# pcb-meter.net
KiCad netlist of a schematic drawn in EAGLE
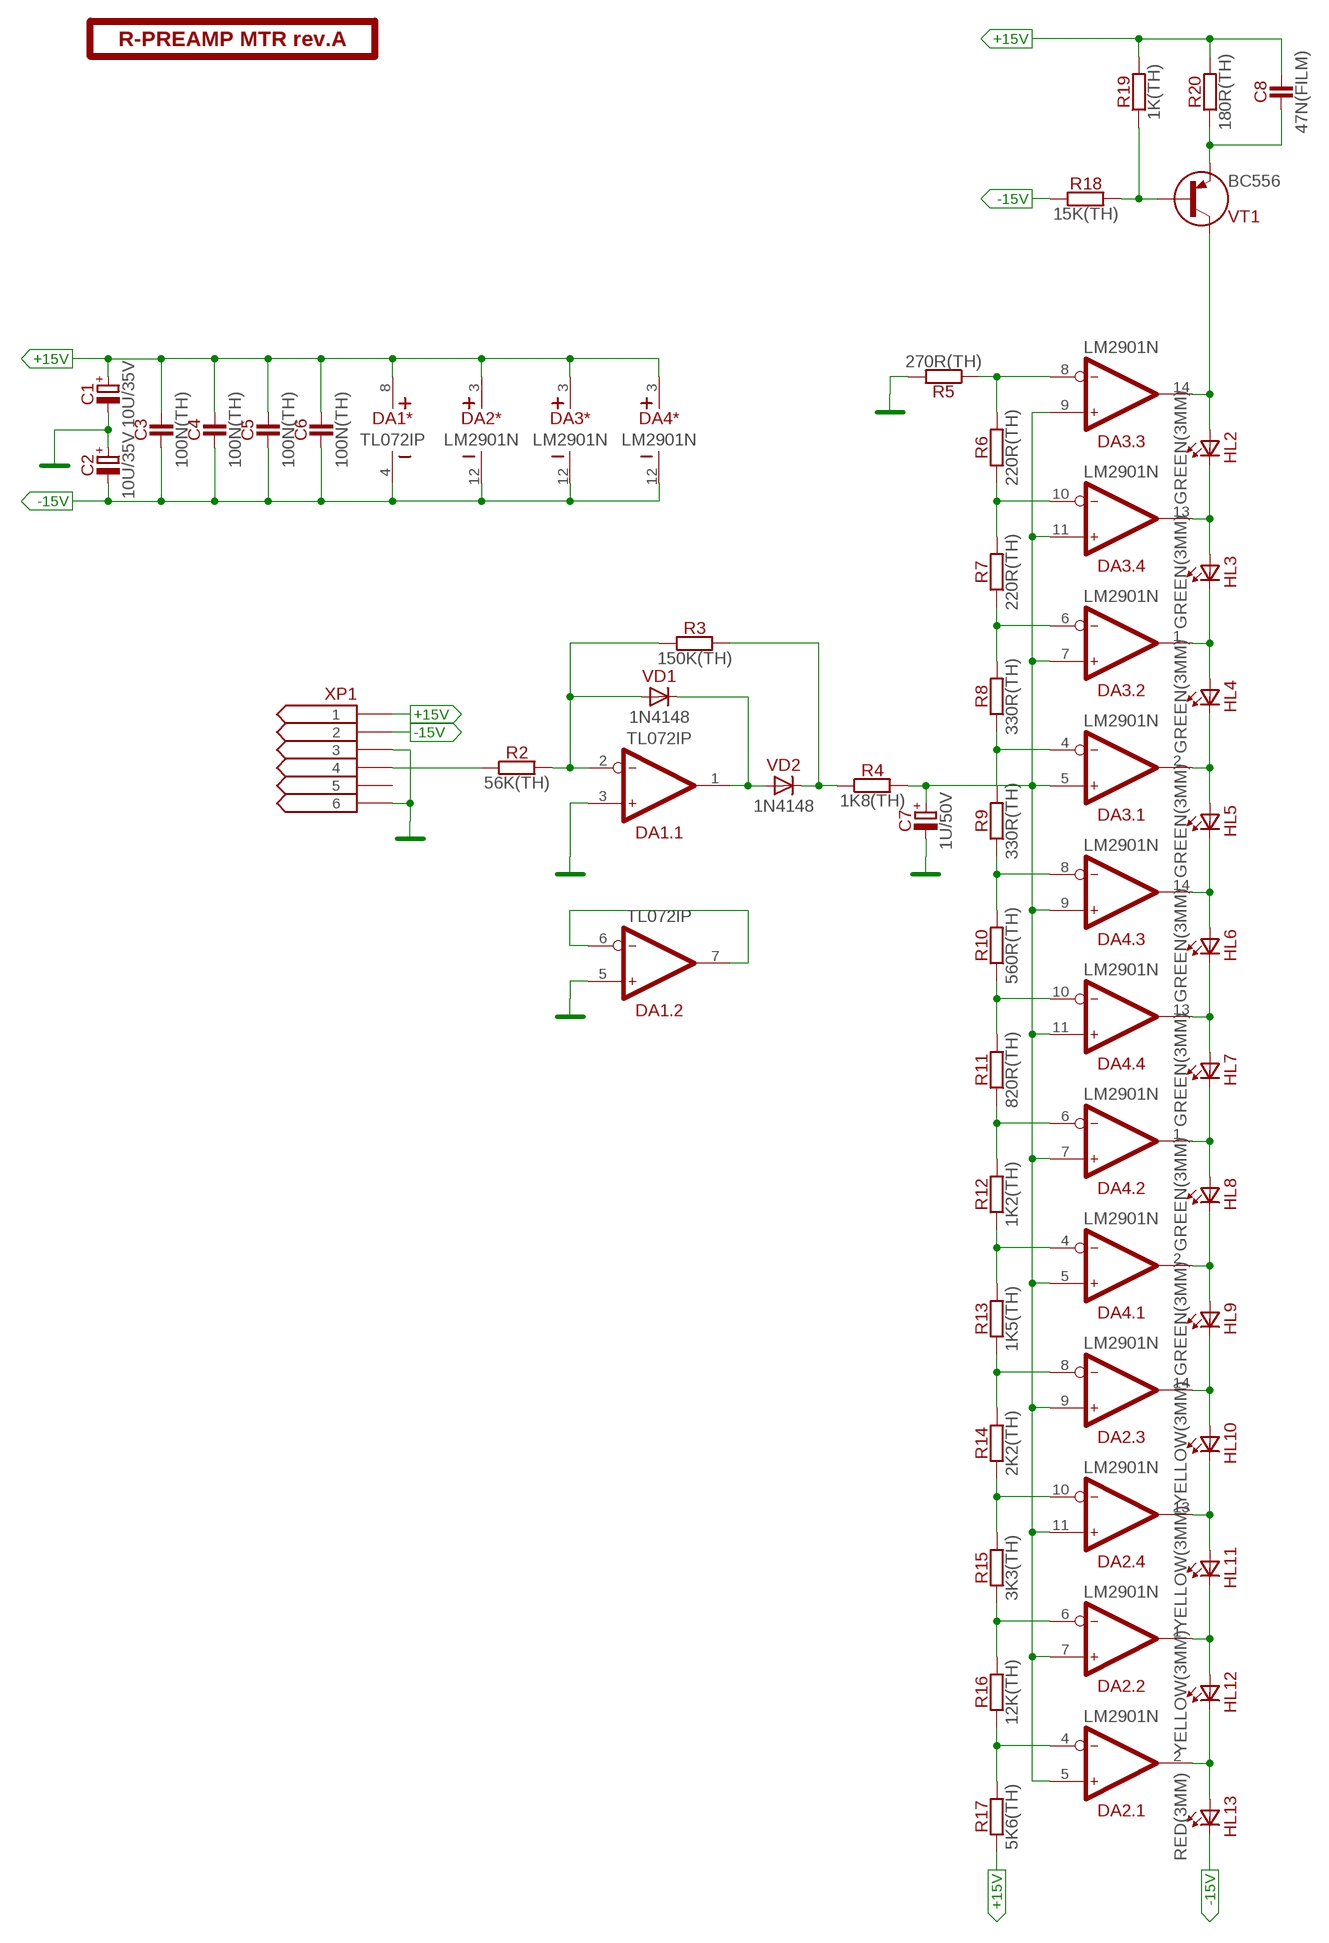
[diagram p0: schematic, sheet 1]

(export (version "E")
  (design (tool "Eeschema 10.0.6"))
  (components
    (comp (ref "C1")
      (value "10U/35V")
      (footprint "eagle-import:E2-5")
      (libsource (lib "eagle-import") (part "?10U/35V"))
    )
    (comp (ref "C2")
      (value "10U/35V")
      (footprint "eagle-import:E2-5")
      (libsource (lib "eagle-import") (part "?10U/35V"))
    )
    (comp (ref "C3")
      (value "100N(TH)")
      (footprint "eagle-import:C050-024X044")
      (libsource (lib "eagle-import") (part "?100N(TH)"))
    )
    (comp (ref "C4")
      (value "100N(TH)")
      (footprint "eagle-import:C050-024X044")
      (libsource (lib "eagle-import") (part "?100N(TH)"))
    )
    (comp (ref "C5")
      (value "100N(TH)")
      (footprint "eagle-import:C050-024X044")
      (libsource (lib "eagle-import") (part "?100N(TH)"))
    )
    (comp (ref "C6")
      (value "100N(TH)")
      (footprint "eagle-import:C050-024X044")
      (libsource (lib "eagle-import") (part "?100N(TH)"))
    )
    (comp (ref "C7")
      (value "1U/50V")
      (footprint "eagle-import:E1,5-4")
      (libsource (lib "eagle-import") (part "?1U/50V"))
    )
    (comp (ref "C8")
      (value "47N(FILM)")
      (footprint "eagle-import:C050-025X075")
      (libsource (lib "eagle-import") (part "?47N(FILM)"))
    )
    (comp (ref "DA1")
      (value "TL072IP")
      (footprint "eagle-import:DIP-8")
      (libsource (lib "eagle-import") (part "TL072IP"))
    )
    (comp (ref "DA2")
      (value "LM2901N")
      (footprint "eagle-import:DIP-14")
      (libsource (lib "eagle-import") (part "LM2901N"))
    )
    (comp (ref "DA3")
      (value "LM2901N")
      (footprint "eagle-import:DIP-14")
      (libsource (lib "eagle-import") (part "LM2901N"))
    )
    (comp (ref "DA4")
      (value "LM2901N")
      (footprint "eagle-import:DIP-14")
      (libsource (lib "eagle-import") (part "LM2901N"))
    )
    (comp (ref "HL2")
      (value "GREEN(3MM)")
      (footprint "eagle-import:LED3MM-H")
      (libsource (lib "eagle-import") (part "?(3MM)GREEN"))
    )
    (comp (ref "HL3")
      (value "GREEN(3MM)")
      (footprint "eagle-import:LED3MM-H")
      (libsource (lib "eagle-import") (part "?(3MM)GREEN"))
    )
    (comp (ref "HL4")
      (value "GREEN(3MM)")
      (footprint "eagle-import:LED3MM-H")
      (libsource (lib "eagle-import") (part "?(3MM)GREEN"))
    )
    (comp (ref "HL5")
      (value "GREEN(3MM)")
      (footprint "eagle-import:LED3MM-H")
      (libsource (lib "eagle-import") (part "?(3MM)GREEN"))
    )
    (comp (ref "HL6")
      (value "GREEN(3MM)")
      (footprint "eagle-import:LED3MM-H")
      (libsource (lib "eagle-import") (part "?(3MM)GREEN"))
    )
    (comp (ref "HL7")
      (value "GREEN(3MM)")
      (footprint "eagle-import:LED3MM-H")
      (libsource (lib "eagle-import") (part "?(3MM)GREEN"))
    )
    (comp (ref "HL8")
      (value "GREEN(3MM)")
      (footprint "eagle-import:LED3MM-H")
      (libsource (lib "eagle-import") (part "?(3MM)GREEN"))
    )
    (comp (ref "HL9")
      (value "GREEN(3MM)")
      (footprint "eagle-import:LED3MM-H")
      (libsource (lib "eagle-import") (part "?(3MM)GREEN"))
    )
    (comp (ref "HL10")
      (value "YELLOW(3MM)")
      (footprint "eagle-import:LED3MM-H")
      (libsource (lib "eagle-import") (part "?(3MM)YELLOW"))
    )
    (comp (ref "HL11")
      (value "YELLOW(3MM)")
      (footprint "eagle-import:LED3MM-H")
      (libsource (lib "eagle-import") (part "?(3MM)YELLOW"))
    )
    (comp (ref "HL12")
      (value "YELLOW(3MM)")
      (footprint "eagle-import:LED3MM-H")
      (libsource (lib "eagle-import") (part "?(3MM)YELLOW"))
    )
    (comp (ref "HL13")
      (value "RED(3MM)")
      (footprint "eagle-import:LED3MM-H")
      (libsource (lib "eagle-import") (part "?(3MM)RED"))
    )
    (comp (ref "PCB1")
      (value "R-PREAMP MTR rev.A")
      (footprint "eagle-import:F-LOGO")
      (libsource (lib "eagle-import") (part "GENERIC-LOGO"))
    )
    (comp (ref "R2")
      (value "56K(TH)")
      (footprint "eagle-import:R-0207_10")
      (libsource (lib "eagle-import") (part "?56K(TH)"))
    )
    (comp (ref "R3")
      (value "150K(TH)")
      (footprint "eagle-import:R-0207_10")
      (libsource (lib "eagle-import") (part "?150K(TH)"))
    )
    (comp (ref "R4")
      (value "1K8(TH)")
      (footprint "eagle-import:R-0207_10")
      (libsource (lib "eagle-import") (part "?1K8(TH)"))
    )
    (comp (ref "R5")
      (value "270R(TH)")
      (footprint "eagle-import:R-0207_10")
      (libsource (lib "eagle-import") (part "?270R(TH)"))
    )
    (comp (ref "R6")
      (value "220R(TH)")
      (footprint "eagle-import:R-0207_10")
      (libsource (lib "eagle-import") (part "?220R(TH)"))
    )
    (comp (ref "R7")
      (value "220R(TH)")
      (footprint "eagle-import:R-0207_10")
      (libsource (lib "eagle-import") (part "?220R(TH)"))
    )
    (comp (ref "R8")
      (value "330R(TH)")
      (footprint "eagle-import:R-0207_10")
      (libsource (lib "eagle-import") (part "?330R(TH)"))
    )
    (comp (ref "R9")
      (value "330R(TH)")
      (footprint "eagle-import:R-0207_10")
      (libsource (lib "eagle-import") (part "?330R(TH)"))
    )
    (comp (ref "R10")
      (value "560R(TH)")
      (footprint "eagle-import:R-0207_10")
      (libsource (lib "eagle-import") (part "?560R(TH)"))
    )
    (comp (ref "R11")
      (value "820R(TH)")
      (footprint "eagle-import:R-0207_10")
      (libsource (lib "eagle-import") (part "?820R(TH)"))
    )
    (comp (ref "R12")
      (value "1K2(TH)")
      (footprint "eagle-import:R-0207_10")
      (libsource (lib "eagle-import") (part "?1K2(TH)"))
    )
    (comp (ref "R13")
      (value "1K5(TH)")
      (footprint "eagle-import:R-0207_10")
      (libsource (lib "eagle-import") (part "?1K5(TH)"))
    )
    (comp (ref "R14")
      (value "2K2(TH)")
      (footprint "eagle-import:R-0207_10")
      (libsource (lib "eagle-import") (part "?2K2(TH)"))
    )
    (comp (ref "R15")
      (value "3K3(TH)")
      (footprint "eagle-import:R-0207_10")
      (libsource (lib "eagle-import") (part "?3K3(TH)"))
    )
    (comp (ref "R16")
      (value "12K(TH)")
      (footprint "eagle-import:R-0207_10")
      (libsource (lib "eagle-import") (part "?12K(TH)"))
    )
    (comp (ref "R17")
      (value "5K6(TH)")
      (footprint "eagle-import:R-0207_10")
      (libsource (lib "eagle-import") (part "?5K6(TH)"))
    )
    (comp (ref "R18")
      (value "15K(TH)")
      (footprint "eagle-import:R-0207_10")
      (libsource (lib "eagle-import") (part "?15K(TH)"))
    )
    (comp (ref "R19")
      (value "1K(TH)")
      (footprint "eagle-import:R-0207_10")
      (libsource (lib "eagle-import") (part "?1K(TH)"))
    )
    (comp (ref "R20")
      (value "180R(TH)")
      (footprint "eagle-import:R-0207_10")
      (libsource (lib "eagle-import") (part "?180R(TH)"))
    )
    (comp (ref "VD1")
      (value "1N4148")
      (footprint "eagle-import:DO35-7")
      (libsource (lib "eagle-import") (part "?1N4148"))
    )
    (comp (ref "VD2")
      (value "1N4148")
      (footprint "eagle-import:DO35-7")
      (libsource (lib "eagle-import") (part "?1N4148"))
    )
    (comp (ref "VT1")
      (value "BC556")
      (footprint "eagle-import:TO92")
      (libsource (lib "eagle-import") (part "?BC556"))
    )
    (comp (ref "XP1")
      (value "CONN-6-NORMAL")
      (footprint "eagle-import:MA03-2")
      (libsource (lib "eagle-import") (part "CONN-6-?NORMAL"))
    )
  )
  (nets
    (net (code "1") (name "+15V") (class "Default")
      (node (ref "C1") (pin "+") (pinfunction "+_+") (pintype "passive"))
      (node (ref "C3") (pin "2") (pinfunction "2_2") (pintype "passive"))
      (node (ref "C4") (pin "2") (pinfunction "2_2") (pintype "passive"))
      (node (ref "C5") (pin "2") (pinfunction "2_2") (pintype "passive"))
      (node (ref "C6") (pin "2") (pinfunction "2_2") (pintype "passive"))
      (node (ref "C8") (pin "2") (pinfunction "2_2") (pintype "passive"))
      (node (ref "DA1") (pin "8") (pinfunction "V+_8") (pintype "power_in"))
      (node (ref "DA2") (pin "3") (pinfunction "V+_3") (pintype "power_in"))
      (node (ref "DA3") (pin "3") (pinfunction "V+_3") (pintype "power_in"))
      (node (ref "DA4") (pin "3") (pinfunction "V+_3") (pintype "power_in"))
      (node (ref "R17") (pin "1") (pinfunction "1_1") (pintype "passive"))
      (node (ref "R19") (pin "2") (pinfunction "2_2") (pintype "passive"))
      (node (ref "R20") (pin "2") (pinfunction "2_2") (pintype "passive"))
      (node (ref "XP1") (pin "1") (pinfunction "1_1") (pintype "passive"))
    )
    (net (code "2") (name "-15V") (class "Default")
      (node (ref "C2") (pin "-") (pinfunction "-_-") (pintype "passive"))
      (node (ref "C3") (pin "1") (pinfunction "1_1") (pintype "passive"))
      (node (ref "C4") (pin "1") (pinfunction "1_1") (pintype "passive"))
      (node (ref "C5") (pin "1") (pinfunction "1_1") (pintype "passive"))
      (node (ref "C6") (pin "1") (pinfunction "1_1") (pintype "passive"))
      (node (ref "DA1") (pin "4") (pinfunction "V-_4") (pintype "power_in"))
      (node (ref "DA2") (pin "12") (pinfunction "V-_12") (pintype "power_in"))
      (node (ref "DA3") (pin "12") (pinfunction "V-_12") (pintype "power_in"))
      (node (ref "DA4") (pin "12") (pinfunction "V-_12") (pintype "power_in"))
      (node (ref "HL13") (pin "K") (pinfunction "C_K") (pintype "passive"))
      (node (ref "R18") (pin "1") (pinfunction "1_1") (pintype "passive"))
      (node (ref "XP1") (pin "2") (pinfunction "2_2") (pintype "passive"))
    )
    (net (code "3") (name "GND") (class "Default")
      (node (ref "C1") (pin "-") (pinfunction "-_-") (pintype "passive"))
      (node (ref "C2") (pin "+") (pinfunction "+_+") (pintype "passive"))
      (node (ref "C7") (pin "-") (pinfunction "-_-") (pintype "passive"))
      (node (ref "DA1") (pin "3") (pinfunction "IN+_3") (pintype "input"))
      (node (ref "DA1") (pin "5") (pinfunction "IN+_5") (pintype "input"))
      (node (ref "R5") (pin "2") (pinfunction "2_2") (pintype "passive"))
      (node (ref "XP1") (pin "3") (pinfunction "3_3") (pintype "passive"))
      (node (ref "XP1") (pin "6") (pinfunction "6_6") (pintype "passive"))
    )
    (net (code "4") (name "Net-(DA1B-IN-)") (class "Default")
      (node (ref "DA1") (pin "2") (pinfunction "IN-_2") (pintype "input"))
      (node (ref "R2") (pin "2") (pinfunction "2_2") (pintype "passive"))
      (node (ref "R3") (pin "1") (pinfunction "1_1") (pintype "passive"))
      (node (ref "VD1") (pin "A") (pinfunction "A_A") (pintype "passive"))
    )
    (net (code "5") (name "Net-(DA1B-OUT)") (class "Default")
      (node (ref "DA1") (pin "1") (pinfunction "OUT_1") (pintype "output"))
      (node (ref "VD1") (pin "C") (pinfunction "C_C") (pintype "passive"))
      (node (ref "VD2") (pin "A") (pinfunction "A_A") (pintype "passive"))
    )
    (net (code "6") (name "Net-(DA1C-IN-)") (class "Default")
      (node (ref "DA1") (pin "6") (pinfunction "IN-_6") (pintype "input"))
      (node (ref "DA1") (pin "7") (pinfunction "OUT_7") (pintype "output"))
    )
    (net (code "7") (name "Net-(DA2B-IN+)") (class "Default")
      (node (ref "C7") (pin "+") (pinfunction "+_+") (pintype "passive"))
      (node (ref "DA2") (pin "11") (pinfunction "IN+_11") (pintype "input"))
      (node (ref "DA2") (pin "5") (pinfunction "IN+_5") (pintype "input"))
      (node (ref "DA2") (pin "7") (pinfunction "IN+_7") (pintype "input"))
      (node (ref "DA2") (pin "9") (pinfunction "IN+_9") (pintype "input"))
      (node (ref "DA3") (pin "11") (pinfunction "IN+_11") (pintype "input"))
      (node (ref "DA3") (pin "5") (pinfunction "IN+_5") (pintype "input"))
      (node (ref "DA3") (pin "7") (pinfunction "IN+_7") (pintype "input"))
      (node (ref "DA3") (pin "9") (pinfunction "IN+_9") (pintype "input"))
      (node (ref "DA4") (pin "11") (pinfunction "IN+_11") (pintype "input"))
      (node (ref "DA4") (pin "5") (pinfunction "IN+_5") (pintype "input"))
      (node (ref "DA4") (pin "7") (pinfunction "IN+_7") (pintype "input"))
      (node (ref "DA4") (pin "9") (pinfunction "IN+_9") (pintype "input"))
      (node (ref "R4") (pin "2") (pinfunction "2_2") (pintype "passive"))
    )
    (net (code "8") (name "Net-(DA2B-IN-)") (class "Default")
      (node (ref "DA2") (pin "4") (pinfunction "IN-_4") (pintype "input"))
      (node (ref "R16") (pin "1") (pinfunction "1_1") (pintype "passive"))
      (node (ref "R17") (pin "2") (pinfunction "2_2") (pintype "passive"))
    )
    (net (code "9") (name "Net-(DA2B-OUT)") (class "Default")
      (node (ref "DA2") (pin "2") (pinfunction "OUT_2") (pintype "output"))
      (node (ref "HL12") (pin "K") (pinfunction "C_K") (pintype "passive"))
      (node (ref "HL13") (pin "A") (pinfunction "A_A") (pintype "passive"))
    )
    (net (code "10") (name "Net-(DA2C-IN-)") (class "Default")
      (node (ref "DA2") (pin "6") (pinfunction "IN-_6") (pintype "input"))
      (node (ref "R15") (pin "1") (pinfunction "1_1") (pintype "passive"))
      (node (ref "R16") (pin "2") (pinfunction "2_2") (pintype "passive"))
    )
    (net (code "11") (name "Net-(DA2C-OUT)") (class "Default")
      (node (ref "DA2") (pin "1") (pinfunction "OUT_1") (pintype "output"))
      (node (ref "HL11") (pin "K") (pinfunction "C_K") (pintype "passive"))
      (node (ref "HL12") (pin "A") (pinfunction "A_A") (pintype "passive"))
    )
    (net (code "12") (name "Net-(DA2D-IN-)") (class "Default")
      (node (ref "DA2") (pin "8") (pinfunction "IN-_8") (pintype "input"))
      (node (ref "R13") (pin "1") (pinfunction "1_1") (pintype "passive"))
      (node (ref "R14") (pin "2") (pinfunction "2_2") (pintype "passive"))
    )
    (net (code "13") (name "Net-(DA2D-OUT)") (class "Default")
      (node (ref "DA2") (pin "14") (pinfunction "OUT_14") (pintype "output"))
      (node (ref "HL10") (pin "A") (pinfunction "A_A") (pintype "passive"))
      (node (ref "HL9") (pin "K") (pinfunction "C_K") (pintype "passive"))
    )
    (net (code "14") (name "Net-(DA2E-IN-)") (class "Default")
      (node (ref "DA2") (pin "10") (pinfunction "IN-_10") (pintype "input"))
      (node (ref "R14") (pin "1") (pinfunction "1_1") (pintype "passive"))
      (node (ref "R15") (pin "2") (pinfunction "2_2") (pintype "passive"))
    )
    (net (code "15") (name "Net-(DA2E-OUT)") (class "Default")
      (node (ref "DA2") (pin "13") (pinfunction "OUT_13") (pintype "output"))
      (node (ref "HL10") (pin "K") (pinfunction "C_K") (pintype "passive"))
      (node (ref "HL11") (pin "A") (pinfunction "A_A") (pintype "passive"))
    )
    (net (code "16") (name "Net-(DA3B-IN-)") (class "Default")
      (node (ref "DA3") (pin "4") (pinfunction "IN-_4") (pintype "input"))
      (node (ref "R8") (pin "1") (pinfunction "1_1") (pintype "passive"))
      (node (ref "R9") (pin "2") (pinfunction "2_2") (pintype "passive"))
    )
    (net (code "17") (name "Net-(DA3B-OUT)") (class "Default")
      (node (ref "DA3") (pin "2") (pinfunction "OUT_2") (pintype "output"))
      (node (ref "HL4") (pin "K") (pinfunction "C_K") (pintype "passive"))
      (node (ref "HL5") (pin "A") (pinfunction "A_A") (pintype "passive"))
    )
    (net (code "18") (name "Net-(DA3C-IN-)") (class "Default")
      (node (ref "DA3") (pin "6") (pinfunction "IN-_6") (pintype "input"))
      (node (ref "R7") (pin "1") (pinfunction "1_1") (pintype "passive"))
      (node (ref "R8") (pin "2") (pinfunction "2_2") (pintype "passive"))
    )
    (net (code "19") (name "Net-(DA3C-OUT)") (class "Default")
      (node (ref "DA3") (pin "1") (pinfunction "OUT_1") (pintype "output"))
      (node (ref "HL3") (pin "K") (pinfunction "C_K") (pintype "passive"))
      (node (ref "HL4") (pin "A") (pinfunction "A_A") (pintype "passive"))
    )
    (net (code "20") (name "Net-(DA3D-IN-)") (class "Default")
      (node (ref "DA3") (pin "8") (pinfunction "IN-_8") (pintype "input"))
      (node (ref "R5") (pin "1") (pinfunction "1_1") (pintype "passive"))
      (node (ref "R6") (pin "2") (pinfunction "2_2") (pintype "passive"))
    )
    (net (code "21") (name "Net-(DA3D-OUT)") (class "Default")
      (node (ref "DA3") (pin "14") (pinfunction "OUT_14") (pintype "output"))
      (node (ref "HL2") (pin "A") (pinfunction "A_A") (pintype "passive"))
      (node (ref "VT1") (pin "1") (pinfunction "C_1") (pintype "passive"))
    )
    (net (code "22") (name "Net-(DA3E-IN-)") (class "Default")
      (node (ref "DA3") (pin "10") (pinfunction "IN-_10") (pintype "input"))
      (node (ref "R6") (pin "1") (pinfunction "1_1") (pintype "passive"))
      (node (ref "R7") (pin "2") (pinfunction "2_2") (pintype "passive"))
    )
    (net (code "23") (name "Net-(DA3E-OUT)") (class "Default")
      (node (ref "DA3") (pin "13") (pinfunction "OUT_13") (pintype "output"))
      (node (ref "HL2") (pin "K") (pinfunction "C_K") (pintype "passive"))
      (node (ref "HL3") (pin "A") (pinfunction "A_A") (pintype "passive"))
    )
    (net (code "24") (name "Net-(DA4B-IN-)") (class "Default")
      (node (ref "DA4") (pin "4") (pinfunction "IN-_4") (pintype "input"))
      (node (ref "R12") (pin "1") (pinfunction "1_1") (pintype "passive"))
      (node (ref "R13") (pin "2") (pinfunction "2_2") (pintype "passive"))
    )
    (net (code "25") (name "Net-(DA4B-OUT)") (class "Default")
      (node (ref "DA4") (pin "2") (pinfunction "OUT_2") (pintype "output"))
      (node (ref "HL8") (pin "K") (pinfunction "C_K") (pintype "passive"))
      (node (ref "HL9") (pin "A") (pinfunction "A_A") (pintype "passive"))
    )
    (net (code "26") (name "Net-(DA4C-IN-)") (class "Default")
      (node (ref "DA4") (pin "6") (pinfunction "IN-_6") (pintype "input"))
      (node (ref "R11") (pin "1") (pinfunction "1_1") (pintype "passive"))
      (node (ref "R12") (pin "2") (pinfunction "2_2") (pintype "passive"))
    )
    (net (code "27") (name "Net-(DA4C-OUT)") (class "Default")
      (node (ref "DA4") (pin "1") (pinfunction "OUT_1") (pintype "output"))
      (node (ref "HL7") (pin "K") (pinfunction "C_K") (pintype "passive"))
      (node (ref "HL8") (pin "A") (pinfunction "A_A") (pintype "passive"))
    )
    (net (code "28") (name "Net-(DA4D-IN-)") (class "Default")
      (node (ref "DA4") (pin "8") (pinfunction "IN-_8") (pintype "input"))
      (node (ref "R10") (pin "2") (pinfunction "2_2") (pintype "passive"))
      (node (ref "R9") (pin "1") (pinfunction "1_1") (pintype "passive"))
    )
    (net (code "29") (name "Net-(DA4D-OUT)") (class "Default")
      (node (ref "DA4") (pin "14") (pinfunction "OUT_14") (pintype "output"))
      (node (ref "HL5") (pin "K") (pinfunction "C_K") (pintype "passive"))
      (node (ref "HL6") (pin "A") (pinfunction "A_A") (pintype "passive"))
    )
    (net (code "30") (name "Net-(DA4E-IN-)") (class "Default")
      (node (ref "DA4") (pin "10") (pinfunction "IN-_10") (pintype "input"))
      (node (ref "R10") (pin "1") (pinfunction "1_1") (pintype "passive"))
      (node (ref "R11") (pin "2") (pinfunction "2_2") (pintype "passive"))
    )
    (net (code "31") (name "Net-(DA4E-OUT)") (class "Default")
      (node (ref "DA4") (pin "13") (pinfunction "OUT_13") (pintype "output"))
      (node (ref "HL6") (pin "K") (pinfunction "C_K") (pintype "passive"))
      (node (ref "HL7") (pin "A") (pinfunction "A_A") (pintype "passive"))
    )
    (net (code "32") (name "Net-(R2-Pad1)") (class "Default")
      (node (ref "R2") (pin "1") (pinfunction "1_1") (pintype "passive"))
      (node (ref "XP1") (pin "4") (pinfunction "4_4") (pintype "passive"))
    )
    (net (code "33") (name "Net-(R3-Pad2)") (class "Default")
      (node (ref "R3") (pin "2") (pinfunction "2_2") (pintype "passive"))
      (node (ref "R4") (pin "1") (pinfunction "1_1") (pintype "passive"))
      (node (ref "VD2") (pin "C") (pinfunction "C_C") (pintype "passive"))
    )
    (net (code "34") (name "Net-(VT1-B)") (class "Default")
      (node (ref "R18") (pin "2") (pinfunction "2_2") (pintype "passive"))
      (node (ref "R19") (pin "1") (pinfunction "1_1") (pintype "passive"))
      (node (ref "VT1") (pin "2") (pinfunction "B_2") (pintype "passive"))
    )
    (net (code "35") (name "Net-(VT1-E)") (class "Default")
      (node (ref "C8") (pin "1") (pinfunction "1_1") (pintype "passive"))
      (node (ref "R20") (pin "1") (pinfunction "1_1") (pintype "passive"))
      (node (ref "VT1") (pin "3") (pinfunction "E_3") (pintype "passive"))
    )
    (net (code "36") (name "unconnected-(XP1-Pad5)") (class "Default")
      (node (ref "XP1") (pin "5") (pinfunction "5_5") (pintype "passive"))
    )
  )
)
